# EthernetShield.net
KiCad netlist of a schematic drawn in EAGLE
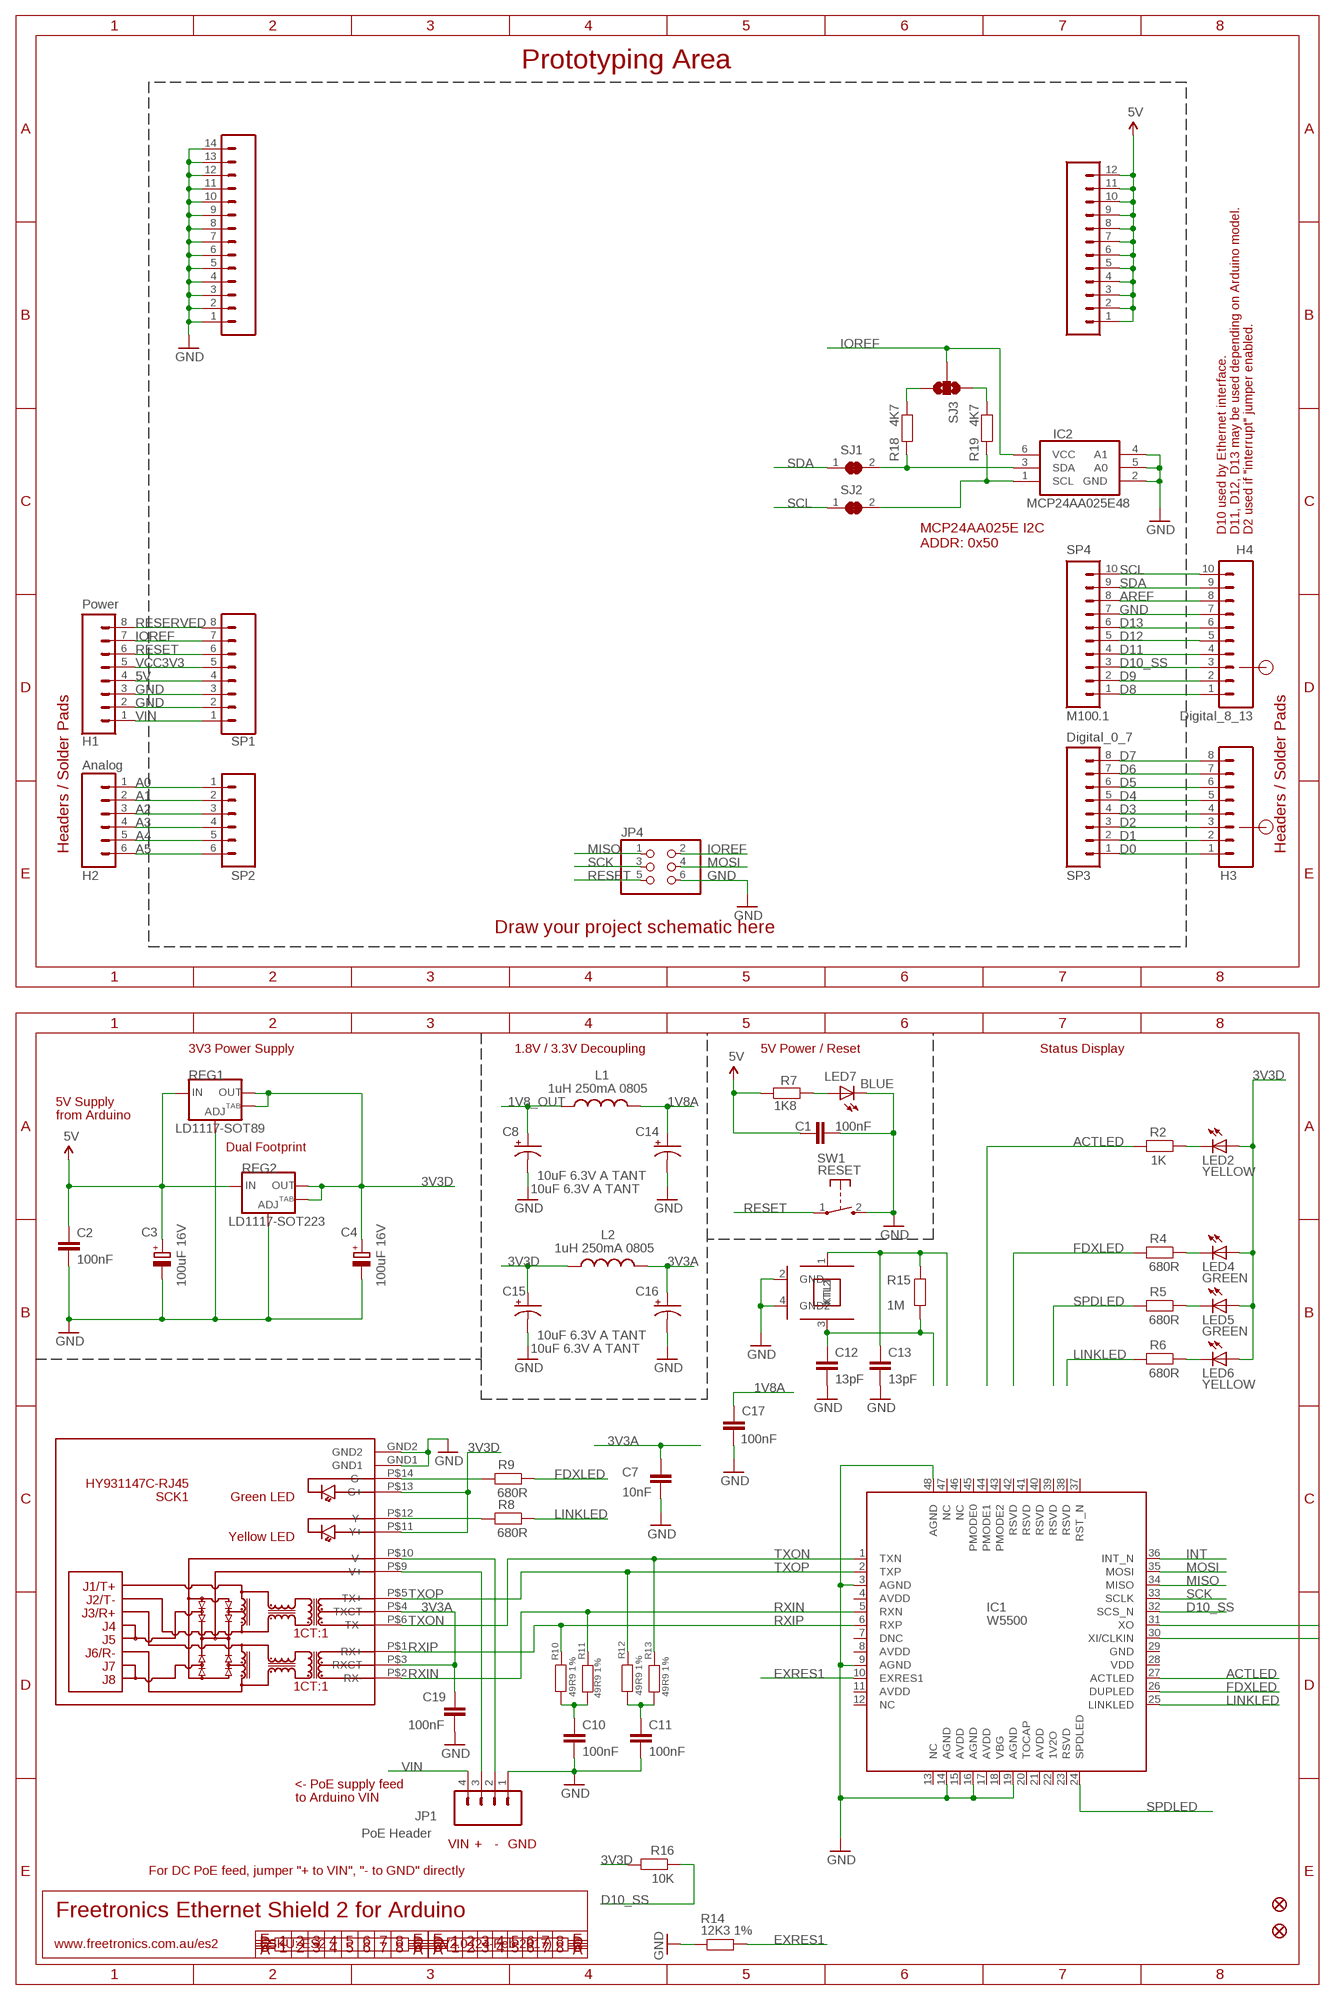
[diagram p0: schematic, sheet 1]

(export (version "E")
  (design (tool "Eeschema 10.0.6"))
  (components
    (comp (ref "C1")
      (value "100nF")
      (footprint "eagle-import:0603")
      (libsource (lib "eagle-import") (part "CAP0603"))
    )
    (comp (ref "C2")
      (value "100nF")
      (footprint "eagle-import:0603")
      (libsource (lib "eagle-import") (part "CAP0603"))
    )
    (comp (ref "C3")
      (value "100uF 16V")
      (footprint "eagle-import:PANASONIC_D")
      (libsource (lib "eagle-import") (part "CPOL-EUD"))
    )
    (comp (ref "C4")
      (value "100uF 16V")
      (footprint "eagle-import:PANASONIC_D")
      (libsource (lib "eagle-import") (part "CPOL-EUD"))
    )
    (comp (ref "C7")
      (value "10nF")
      (footprint "eagle-import:0603")
      (libsource (lib "eagle-import") (part "CAP0603"))
    )
    (comp (ref "C8")
      (value "10uF 6.3V A TANT")
      (footprint "eagle-import:EIA3216")
      (libsource (lib "eagle-import") (part "CAP_POL1206"))
    )
    (comp (ref "C10")
      (value "100nF")
      (footprint "eagle-import:0603")
      (libsource (lib "eagle-import") (part "CAP0603"))
    )
    (comp (ref "C11")
      (value "100nF")
      (footprint "eagle-import:0603")
      (libsource (lib "eagle-import") (part "CAP0603"))
    )
    (comp (ref "C12")
      (value "13pF")
      (footprint "eagle-import:0603")
      (libsource (lib "eagle-import") (part "CAP0603"))
    )
    (comp (ref "C13")
      (value "13pF")
      (footprint "eagle-import:0603")
      (libsource (lib "eagle-import") (part "CAP0603"))
    )
    (comp (ref "C14")
      (value "10uF 6.3V A TANT")
      (footprint "eagle-import:EIA3216")
      (libsource (lib "eagle-import") (part "CAP_POL1206"))
    )
    (comp (ref "C15")
      (value "10uF 6.3V A TANT")
      (footprint "eagle-import:EIA3216")
      (libsource (lib "eagle-import") (part "CAP_POL1206"))
    )
    (comp (ref "C16")
      (value "10uF 6.3V A TANT")
      (footprint "eagle-import:EIA3216")
      (libsource (lib "eagle-import") (part "CAP_POL1206"))
    )
    (comp (ref "C17")
      (value "100nF")
      (footprint "eagle-import:0603")
      (libsource (lib "eagle-import") (part "CAP0603"))
    )
    (comp (ref "C19")
      (value "100nF")
      (footprint "eagle-import:0603")
      (libsource (lib "eagle-import") (part "CAP0603"))
    )
    (comp (ref "H1")
      (value "Power")
      (footprint "eagle-import:1X08")
      (libsource (lib "eagle-import") (part "M08"))
    )
    (comp (ref "H2")
      (value "Analog")
      (footprint "eagle-import:1X06")
      (libsource (lib "eagle-import") (part "M06SIP"))
    )
    (comp (ref "H3")
      (value "Digital_0_7")
      (footprint "eagle-import:1X08")
      (libsource (lib "eagle-import") (part "M08"))
    )
    (comp (ref "H4")
      (value "Digital_8_13")
      (footprint "eagle-import:1X10")
      (libsource (lib "eagle-import") (part "M100.1"))
    )
    (comp (ref "IC1")
      (value "W5500")
      (footprint "eagle-import:W5500")
      (libsource (lib "eagle-import") (part "W5500"))
    )
    (comp (ref "IC2")
      (value "MCP24AA025E48")
      (footprint "eagle-import:SOT23-6")
      (libsource (lib "eagle-import") (part "MCP24AA025E48"))
    )
    (comp (ref "JP1")
      (value "PoE Header")
      (footprint "eagle-import:1X04")
      (libsource (lib "eagle-import") (part "M04PTH"))
    )
    (comp (ref "JP4")
      (value "PINHD-2X3")
      (footprint "eagle-import:2X03")
      (libsource (lib "eagle-import") (part "PINHD-2X3"))
    )
    (comp (ref "L1")
      (value "1uH 250mA 0805")
      (footprint "eagle-import:L2012C")
      (libsource (lib "eagle-import") (part "L-USL2012C"))
    )
    (comp (ref "L2")
      (value "1uH 250mA 0805")
      (footprint "eagle-import:L2012C")
      (libsource (lib "eagle-import") (part "L-USL2012C"))
    )
    (comp (ref "LED2")
      (value "YELLOW")
      (footprint "eagle-import:LED-0603")
      (libsource (lib "eagle-import") (part "LED0603"))
    )
    (comp (ref "LED4")
      (value "GREEN")
      (footprint "eagle-import:LED-0603")
      (libsource (lib "eagle-import") (part "LED0603"))
    )
    (comp (ref "LED5")
      (value "GREEN")
      (footprint "eagle-import:LED-0603")
      (libsource (lib "eagle-import") (part "LED0603"))
    )
    (comp (ref "LED6")
      (value "YELLOW")
      (footprint "eagle-import:LED-0603")
      (libsource (lib "eagle-import") (part "LED0603"))
    )
    (comp (ref "LED7")
      (value "BLUE")
      (footprint "eagle-import:LED-0603")
      (libsource (lib "eagle-import") (part "LED0603"))
    )
    (comp (ref "PADS_5V")
      (value "M12PTH")
      (footprint "eagle-import:1X12")
      (libsource (lib "eagle-import") (part "M12PTH"))
    )
    (comp (ref "PADS_GND")
      (value "M14")
      (footprint "eagle-import:1X14")
      (libsource (lib "eagle-import") (part "M14"))
    )
    (comp (ref "R2")
      (value "1K")
      (footprint "eagle-import:0603")
      (libsource (lib "eagle-import") (part "RESISTOR0603"))
    )
    (comp (ref "R4")
      (value "680R")
      (footprint "eagle-import:0603")
      (libsource (lib "eagle-import") (part "RESISTOR0603"))
    )
    (comp (ref "R5")
      (value "680R")
      (footprint "eagle-import:0603")
      (libsource (lib "eagle-import") (part "RESISTOR0603"))
    )
    (comp (ref "R6")
      (value "680R")
      (footprint "eagle-import:0603")
      (libsource (lib "eagle-import") (part "RESISTOR0603"))
    )
    (comp (ref "R7")
      (value "1K8")
      (footprint "eagle-import:0603")
      (libsource (lib "eagle-import") (part "RESISTOR0603"))
    )
    (comp (ref "R8")
      (value "680R")
      (footprint "eagle-import:0603")
      (libsource (lib "eagle-import") (part "RESISTOR0603"))
    )
    (comp (ref "R9")
      (value "680R")
      (footprint "eagle-import:0603")
      (libsource (lib "eagle-import") (part "RESISTOR0603"))
    )
    (comp (ref "R10")
      (value "49R9 1%")
      (footprint "eagle-import:0603")
      (libsource (lib "eagle-import") (part "RESISTOR0603"))
    )
    (comp (ref "R11")
      (value "49R9 1%")
      (footprint "eagle-import:0603")
      (libsource (lib "eagle-import") (part "RESISTOR0603"))
    )
    (comp (ref "R12")
      (value "49R9 1%")
      (footprint "eagle-import:0603")
      (libsource (lib "eagle-import") (part "RESISTOR0603"))
    )
    (comp (ref "R13")
      (value "49R9 1%")
      (footprint "eagle-import:0603")
      (libsource (lib "eagle-import") (part "RESISTOR0603"))
    )
    (comp (ref "R14")
      (value "12K3 1%")
      (footprint "eagle-import:0603")
      (libsource (lib "eagle-import") (part "RESISTOR0603"))
    )
    (comp (ref "R15")
      (value "1M")
      (footprint "eagle-import:0603")
      (libsource (lib "eagle-import") (part "RESISTOR0603"))
    )
    (comp (ref "R16")
      (value "10K")
      (footprint "eagle-import:0603")
      (libsource (lib "eagle-import") (part "RESISTOR0603"))
    )
    (comp (ref "R18")
      (value "4K7")
      (footprint "eagle-import:0603")
      (libsource (lib "eagle-import") (part "freetronics-master-v1.1_RESISTOR0603"))
    )
    (comp (ref "R19")
      (value "4K7")
      (footprint "eagle-import:0603")
      (libsource (lib "eagle-import") (part "freetronics-master-v1.1_RESISTOR0603"))
    )
    (comp (ref "REG1")
      (value "LD1117-SOT89")
      (footprint "eagle-import:SOT89")
      (libsource (lib "eagle-import") (part "V_REG_LM1117SOT89"))
    )
    (comp (ref "REG2")
      (value "LD1117-SOT223")
      (footprint "eagle-import:SOT223")
      (libsource (lib "eagle-import") (part "V_REG_LM1117SOT223"))
    )
    (comp (ref "SCK1")
      (value "HY931147C-RJ45")
      (footprint "eagle-import:HY931147C")
      (libsource (lib "eagle-import") (part "HY931147C-RJ45"))
    )
    (comp (ref "SJ1")
      (value "SJCN")
      (footprint "eagle-import:SJC")
      (libsource (lib "eagle-import") (part "SJCN"))
    )
    (comp (ref "SJ2")
      (value "SJCN")
      (footprint "eagle-import:SJC")
      (libsource (lib "eagle-import") (part "SJCN"))
    )
    (comp (ref "SJ3")
      (value "SOLDERJUMPER_2WAYT")
      (footprint "eagle-import:SJ_2")
      (libsource (lib "eagle-import") (part "SOLDERJUMPER_2WAYT"))
    )
    (comp (ref "SP1")
      (value "M08")
      (footprint "eagle-import:1X08")
      (libsource (lib "eagle-import") (part "M08"))
    )
    (comp (ref "SP2")
      (value "Analog")
      (footprint "eagle-import:1X06")
      (libsource (lib "eagle-import") (part "M06SIP"))
    )
    (comp (ref "SP3")
      (value "Digital_0_7")
      (footprint "eagle-import:1X08")
      (libsource (lib "eagle-import") (part "M08"))
    )
    (comp (ref "SP4")
      (value "M100.1")
      (footprint "eagle-import:1X10")
      (libsource (lib "eagle-import") (part "M100.1"))
    )
    (comp (ref "SW1")
      (value "RESET")
      (footprint "eagle-import:TACTILE_SWITCH_SMD_2PIN_TINY")
      (libsource (lib "eagle-import") (part "TAC_SWITCH_2PIN"))
    )
    (comp (ref "U$6")
      (value "FIDUCIAL1X2.5")
      (footprint "eagle-import:FIDUCIAL-1X2.5")
      (libsource (lib "eagle-import") (part "FIDUCIAL1X2.5"))
    )
    (comp (ref "U$8")
      (value "FIDUCIAL1X2.5")
      (footprint "eagle-import:FIDUCIAL-1X2.5")
      (libsource (lib "eagle-import") (part "FIDUCIAL1X2.5"))
    )
    (comp (ref "XTL1")
      (value "25MHZ")
      (footprint "eagle-import:CRYSTAL-SMD-3X2")
      (libsource (lib "eagle-import") (part "CRYSTAL-GND3X2"))
    )
  )
  (nets
    (net (code "1") (name "/1V8A") (class "Default")
      (node (ref "C14") (pin "A") (pinfunction "+_A") (pintype "passive"))
      (node (ref "C17") (pin "1") (pinfunction "1_1") (pintype "passive"))
      (node (ref "L1") (pin "2") (pinfunction "2_2") (pintype "passive"))
    )
    (net (code "2") (name "/1V8_OUT") (class "Default")
      (node (ref "C8") (pin "A") (pinfunction "+_A") (pintype "passive"))
      (node (ref "L1") (pin "1") (pinfunction "1_1") (pintype "passive"))
    )
    (net (code "3") (name "/3V3A") (class "Default")
      (node (ref "C16") (pin "A") (pinfunction "+_A") (pintype "passive"))
      (node (ref "C19") (pin "1") (pinfunction "1_1") (pintype "passive"))
      (node (ref "C7") (pin "1") (pinfunction "1_1") (pintype "passive"))
      (node (ref "L2") (pin "2") (pinfunction "2_2") (pintype "passive"))
      (node (ref "SCK1") (pin "P$3") (pinfunction "RXCT_P$3") (pintype "bidirectional"))
      (node (ref "SCK1") (pin "P$4") (pinfunction "TXCT_P$4") (pintype "bidirectional"))
    )
    (net (code "4") (name "/3V3D") (class "Default")
      (node (ref "C15") (pin "A") (pinfunction "+_A") (pintype "passive"))
      (node (ref "C4") (pin "+") (pinfunction "+_+") (pintype "passive"))
      (node (ref "L2") (pin "1") (pinfunction "1_1") (pintype "passive"))
      (node (ref "LED2") (pin "A") (pinfunction "A_A") (pintype "passive"))
      (node (ref "LED4") (pin "A") (pinfunction "A_A") (pintype "passive"))
      (node (ref "LED5") (pin "A") (pinfunction "A_A") (pintype "passive"))
      (node (ref "LED6") (pin "A") (pinfunction "A_A") (pintype "passive"))
      (node (ref "R16") (pin "2") (pinfunction "2_2") (pintype "passive"))
      (node (ref "REG1") (pin "2") (pinfunction "OUT_2") (pintype "output"))
      (node (ref "REG1") (pin "4") (pinfunction "OUT_4") (pintype "output"))
      (node (ref "REG2") (pin "2") (pinfunction "OUT_2") (pintype "output"))
      (node (ref "REG2") (pin "4") (pinfunction "OUT_4") (pintype "output"))
      (node (ref "SCK1") (pin "P$11") (pinfunction "Y+_P$11") (pintype "bidirectional"))
      (node (ref "SCK1") (pin "P$13") (pinfunction "G+_P$13") (pintype "bidirectional"))
    )
    (net (code "5") (name "/A0") (class "Default")
      (node (ref "H2") (pin "1") (pinfunction "1_1") (pintype "passive"))
      (node (ref "SP2") (pin "1") (pinfunction "1_1") (pintype "passive"))
    )
    (net (code "6") (name "/A1") (class "Default")
      (node (ref "H2") (pin "2") (pinfunction "2_2") (pintype "passive"))
      (node (ref "SP2") (pin "2") (pinfunction "2_2") (pintype "passive"))
    )
    (net (code "7") (name "/A2") (class "Default")
      (node (ref "H2") (pin "3") (pinfunction "3_3") (pintype "passive"))
      (node (ref "SP2") (pin "3") (pinfunction "3_3") (pintype "passive"))
    )
    (net (code "8") (name "/A3") (class "Default")
      (node (ref "H2") (pin "4") (pinfunction "4_4") (pintype "passive"))
      (node (ref "SP2") (pin "4") (pinfunction "4_4") (pintype "passive"))
    )
    (net (code "9") (name "/A4") (class "Default")
      (node (ref "H2") (pin "5") (pinfunction "5_5") (pintype "passive"))
      (node (ref "SP2") (pin "5") (pinfunction "5_5") (pintype "passive"))
    )
    (net (code "10") (name "/A5") (class "Default")
      (node (ref "H2") (pin "6") (pinfunction "6_6") (pintype "passive"))
      (node (ref "SP2") (pin "6") (pinfunction "6_6") (pintype "passive"))
    )
    (net (code "11") (name "/ACTLED") (class "Default")
      (node (ref "IC1") (pin "27") (pinfunction "ACTLED_27") (pintype "passive"))
      (node (ref "R2") (pin "2") (pinfunction "2_2") (pintype "passive"))
    )
    (net (code "12") (name "/AREF") (class "Default")
      (node (ref "H4") (pin "8") (pinfunction "8_8") (pintype "passive"))
      (node (ref "SP4") (pin "8") (pinfunction "8_8") (pintype "passive"))
    )
    (net (code "13") (name "/D0") (class "Default")
      (node (ref "H3") (pin "1") (pinfunction "1_1") (pintype "passive"))
      (node (ref "SP3") (pin "1") (pinfunction "1_1") (pintype "passive"))
    )
    (net (code "14") (name "/D1") (class "Default")
      (node (ref "H3") (pin "2") (pinfunction "2_2") (pintype "passive"))
      (node (ref "SP3") (pin "2") (pinfunction "2_2") (pintype "passive"))
    )
    (net (code "15") (name "/D2") (class "Default")
      (node (ref "H3") (pin "3") (pinfunction "3_3") (pintype "passive"))
      (node (ref "SP3") (pin "3") (pinfunction "3_3") (pintype "passive"))
    )
    (net (code "16") (name "/D3") (class "Default")
      (node (ref "H3") (pin "4") (pinfunction "4_4") (pintype "passive"))
      (node (ref "SP3") (pin "4") (pinfunction "4_4") (pintype "passive"))
    )
    (net (code "17") (name "/D4") (class "Default")
      (node (ref "H3") (pin "5") (pinfunction "5_5") (pintype "passive"))
      (node (ref "SP3") (pin "5") (pinfunction "5_5") (pintype "passive"))
    )
    (net (code "18") (name "/D5") (class "Default")
      (node (ref "H3") (pin "6") (pinfunction "6_6") (pintype "passive"))
      (node (ref "SP3") (pin "6") (pinfunction "6_6") (pintype "passive"))
    )
    (net (code "19") (name "/D6") (class "Default")
      (node (ref "H3") (pin "7") (pinfunction "7_7") (pintype "passive"))
      (node (ref "SP3") (pin "7") (pinfunction "7_7") (pintype "passive"))
    )
    (net (code "20") (name "/D7") (class "Default")
      (node (ref "H3") (pin "8") (pinfunction "8_8") (pintype "passive"))
      (node (ref "SP3") (pin "8") (pinfunction "8_8") (pintype "passive"))
    )
    (net (code "21") (name "/D8") (class "Default")
      (node (ref "H4") (pin "1") (pinfunction "1_1") (pintype "passive"))
      (node (ref "SP4") (pin "1") (pinfunction "1_1") (pintype "passive"))
    )
    (net (code "22") (name "/D9") (class "Default")
      (node (ref "H4") (pin "2") (pinfunction "2_2") (pintype "passive"))
      (node (ref "SP4") (pin "2") (pinfunction "2_2") (pintype "passive"))
    )
    (net (code "23") (name "/D10_SS") (class "Default")
      (node (ref "H4") (pin "3") (pinfunction "3_3") (pintype "passive"))
      (node (ref "IC1") (pin "32") (pinfunction "SCS_N_32") (pintype "passive"))
      (node (ref "R16") (pin "1") (pinfunction "1_1") (pintype "passive"))
      (node (ref "SP4") (pin "3") (pinfunction "3_3") (pintype "passive"))
    )
    (net (code "24") (name "/D11") (class "Default")
      (node (ref "H4") (pin "4") (pinfunction "4_4") (pintype "passive"))
      (node (ref "SP4") (pin "4") (pinfunction "4_4") (pintype "passive"))
    )
    (net (code "25") (name "/D12") (class "Default")
      (node (ref "H4") (pin "5") (pinfunction "5_5") (pintype "passive"))
      (node (ref "SP4") (pin "5") (pinfunction "5_5") (pintype "passive"))
    )
    (net (code "26") (name "/D13") (class "Default")
      (node (ref "H4") (pin "6") (pinfunction "6_6") (pintype "passive"))
      (node (ref "SP4") (pin "6") (pinfunction "6_6") (pintype "passive"))
    )
    (net (code "27") (name "/EXRES1") (class "Default")
      (node (ref "IC1") (pin "10") (pinfunction "EXRES1_10") (pintype "passive"))
      (node (ref "R14") (pin "2") (pinfunction "2_2") (pintype "passive"))
    )
    (net (code "28") (name "/FDXLED") (class "Default")
      (node (ref "IC1") (pin "26") (pinfunction "DUPLED_26") (pintype "passive"))
      (node (ref "R4") (pin "2") (pinfunction "2_2") (pintype "passive"))
      (node (ref "R9") (pin "1") (pinfunction "1_1") (pintype "passive"))
    )
    (net (code "29") (name "/INT") (class "Default")
      (node (ref "IC1") (pin "36") (pinfunction "INT_N_36") (pintype "passive"))
    )
    (net (code "30") (name "/IOREF") (class "Default")
      (node (ref "H1") (pin "7") (pinfunction "7_7") (pintype "passive"))
      (node (ref "IC2") (pin "6") (pinfunction "VCC_6") (pintype "power_in"))
      (node (ref "JP4") (pin "2") (pinfunction "2_2") (pintype "passive"))
      (node (ref "SJ3") (pin "2") (pinfunction "2_2") (pintype "passive"))
      (node (ref "SP1") (pin "7") (pinfunction "7_7") (pintype "passive"))
    )
    (net (code "31") (name "/LINKLED") (class "Default")
      (node (ref "IC1") (pin "25") (pinfunction "LINKLED_25") (pintype "passive"))
      (node (ref "R6") (pin "2") (pinfunction "2_2") (pintype "passive"))
      (node (ref "R8") (pin "1") (pinfunction "1_1") (pintype "passive"))
    )
    (net (code "32") (name "/MISO") (class "Default")
      (node (ref "IC1") (pin "34") (pinfunction "MISO_34") (pintype "passive"))
      (node (ref "JP4") (pin "1") (pinfunction "1_1") (pintype "passive"))
    )
    (net (code "33") (name "/MOSI") (class "Default")
      (node (ref "IC1") (pin "35") (pinfunction "MOSI_35") (pintype "passive"))
      (node (ref "JP4") (pin "4") (pinfunction "4_4") (pintype "passive"))
    )
    (net (code "34") (name "/RESERVED") (class "Default")
      (node (ref "H1") (pin "8") (pinfunction "8_8") (pintype "passive"))
      (node (ref "SP1") (pin "8") (pinfunction "8_8") (pintype "passive"))
    )
    (net (code "35") (name "/RESET") (class "Default")
      (node (ref "H1") (pin "6") (pinfunction "6_6") (pintype "passive"))
      (node (ref "JP4") (pin "5") (pinfunction "5_5") (pintype "passive"))
      (node (ref "SP1") (pin "6") (pinfunction "6_6") (pintype "passive"))
      (node (ref "SW1") (pin "1") (pinfunction "P_1") (pintype "passive"))
    )
    (net (code "36") (name "/RXIN") (class "Default")
      (node (ref "IC1") (pin "5") (pinfunction "RXN_5") (pintype "passive"))
      (node (ref "R11") (pin "1") (pinfunction "1_1") (pintype "passive"))
      (node (ref "SCK1") (pin "P$2") (pinfunction "RX-_P$2") (pintype "bidirectional"))
    )
    (net (code "37") (name "/RXIP") (class "Default")
      (node (ref "IC1") (pin "6") (pinfunction "RXP_6") (pintype "passive"))
      (node (ref "R10") (pin "2") (pinfunction "2_2") (pintype "passive"))
      (node (ref "SCK1") (pin "P$1") (pinfunction "RX+_P$1") (pintype "bidirectional"))
    )
    (net (code "38") (name "/SCK") (class "Default")
      (node (ref "IC1") (pin "33") (pinfunction "SCLK_33") (pintype "passive"))
      (node (ref "JP4") (pin "3") (pinfunction "3_3") (pintype "passive"))
    )
    (net (code "39") (name "/SCL") (class "Default")
      (node (ref "H4") (pin "10") (pinfunction "10_10") (pintype "passive"))
      (node (ref "SJ2") (pin "1") (pinfunction "1_1") (pintype "passive"))
      (node (ref "SP4") (pin "10") (pinfunction "10_10") (pintype "passive"))
    )
    (net (code "40") (name "/SDA") (class "Default")
      (node (ref "H4") (pin "9") (pinfunction "9_9") (pintype "passive"))
      (node (ref "SJ1") (pin "1") (pinfunction "1_1") (pintype "passive"))
      (node (ref "SP4") (pin "9") (pinfunction "9_9") (pintype "passive"))
    )
    (net (code "41") (name "/SPDLED") (class "Default")
      (node (ref "IC1") (pin "24") (pinfunction "SPDLED_24") (pintype "passive"))
      (node (ref "R5") (pin "2") (pinfunction "2_2") (pintype "passive"))
    )
    (net (code "42") (name "/TXON") (class "Default")
      (node (ref "IC1") (pin "1") (pinfunction "TXN_1") (pintype "passive"))
      (node (ref "R13") (pin "1") (pinfunction "1_1") (pintype "passive"))
      (node (ref "SCK1") (pin "P$6") (pinfunction "TX-_P$6") (pintype "bidirectional"))
    )
    (net (code "43") (name "/TXOP") (class "Default")
      (node (ref "IC1") (pin "2") (pinfunction "TXP_2") (pintype "passive"))
      (node (ref "R12") (pin "2") (pinfunction "2_2") (pintype "passive"))
      (node (ref "SCK1") (pin "P$5") (pinfunction "TX+_P$5") (pintype "bidirectional"))
    )
    (net (code "44") (name "/VCC3V3") (class "Default")
      (node (ref "H1") (pin "5") (pinfunction "5_5") (pintype "passive"))
      (node (ref "SP1") (pin "5") (pinfunction "5_5") (pintype "passive"))
    )
    (net (code "45") (name "/VIN") (class "Default")
      (node (ref "H1") (pin "1") (pinfunction "1_1") (pintype "passive"))
      (node (ref "JP1") (pin "4") (pinfunction "4_4") (pintype "passive"))
      (node (ref "SP1") (pin "1") (pinfunction "1_1") (pintype "passive"))
    )
    (net (code "46") (name "5V") (class "Default")
      (node (ref "C1") (pin "1") (pinfunction "1_1") (pintype "passive"))
      (node (ref "C2") (pin "1") (pinfunction "1_1") (pintype "passive"))
      (node (ref "C3") (pin "+") (pinfunction "+_+") (pintype "passive"))
      (node (ref "H1") (pin "4") (pinfunction "4_4") (pintype "passive"))
      (node (ref "PADS_5V") (pin "1") (pinfunction "1_1") (pintype "passive"))
      (node (ref "PADS_5V") (pin "10") (pinfunction "10_10") (pintype "passive"))
      (node (ref "PADS_5V") (pin "11") (pinfunction "11_11") (pintype "passive"))
      (node (ref "PADS_5V") (pin "12") (pinfunction "12_12") (pintype "passive"))
      (node (ref "PADS_5V") (pin "2") (pinfunction "2_2") (pintype "passive"))
      (node (ref "PADS_5V") (pin "3") (pinfunction "3_3") (pintype "passive"))
      (node (ref "PADS_5V") (pin "4") (pinfunction "4_4") (pintype "passive"))
      (node (ref "PADS_5V") (pin "5") (pinfunction "5_5") (pintype "passive"))
      (node (ref "PADS_5V") (pin "6") (pinfunction "6_6") (pintype "passive"))
      (node (ref "PADS_5V") (pin "7") (pinfunction "7_7") (pintype "passive"))
      (node (ref "PADS_5V") (pin "8") (pinfunction "8_8") (pintype "passive"))
      (node (ref "PADS_5V") (pin "9") (pinfunction "9_9") (pintype "passive"))
      (node (ref "R7") (pin "1") (pinfunction "1_1") (pintype "passive"))
      (node (ref "REG1") (pin "3") (pinfunction "IN_3") (pintype "input"))
      (node (ref "REG2") (pin "3") (pinfunction "IN_3") (pintype "input"))
      (node (ref "SP1") (pin "4") (pinfunction "4_4") (pintype "passive"))
    )
    (net (code "47") (name "GND") (class "Default")
      (node (ref "C1") (pin "2") (pinfunction "2_2") (pintype "passive"))
      (node (ref "C10") (pin "2") (pinfunction "2_2") (pintype "passive"))
      (node (ref "C11") (pin "2") (pinfunction "2_2") (pintype "passive"))
      (node (ref "C12") (pin "2") (pinfunction "2_2") (pintype "passive"))
      (node (ref "C13") (pin "2") (pinfunction "2_2") (pintype "passive"))
      (node (ref "C14") (pin "C") (pinfunction "-_C") (pintype "passive"))
      (node (ref "C15") (pin "C") (pinfunction "-_C") (pintype "passive"))
      (node (ref "C16") (pin "C") (pinfunction "-_C") (pintype "passive"))
      (node (ref "C17") (pin "2") (pinfunction "2_2") (pintype "passive"))
      (node (ref "C19") (pin "2") (pinfunction "2_2") (pintype "passive"))
      (node (ref "C2") (pin "2") (pinfunction "2_2") (pintype "passive"))
      (node (ref "C3") (pin "-") (pinfunction "-_-") (pintype "passive"))
      (node (ref "C4") (pin "-") (pinfunction "-_-") (pintype "passive"))
      (node (ref "C7") (pin "2") (pinfunction "2_2") (pintype "passive"))
      (node (ref "C8") (pin "C") (pinfunction "-_C") (pintype "passive"))
      (node (ref "H1") (pin "2") (pinfunction "2_2") (pintype "passive"))
      (node (ref "H1") (pin "3") (pinfunction "3_3") (pintype "passive"))
      (node (ref "H4") (pin "7") (pinfunction "7_7") (pintype "passive"))
      (node (ref "IC1") (pin "14") (pinfunction "AGND_14") (pintype "passive"))
      (node (ref "IC1") (pin "16") (pinfunction "AGND_16") (pintype "passive"))
      (node (ref "IC1") (pin "19") (pinfunction "AGND_19") (pintype "passive"))
      (node (ref "IC1") (pin "3") (pinfunction "AGND_3") (pintype "passive"))
      (node (ref "IC1") (pin "48") (pinfunction "AGND_48") (pintype "passive"))
      (node (ref "IC1") (pin "9") (pinfunction "AGND_9") (pintype "passive"))
      (node (ref "IC2") (pin "2") (pinfunction "GND_2") (pintype "power_in"))
      (node (ref "IC2") (pin "4") (pinfunction "A1_4") (pintype "input"))
      (node (ref "IC2") (pin "5") (pinfunction "A0_5") (pintype "input"))
      (node (ref "JP1") (pin "1") (pinfunction "1_1") (pintype "passive"))
      (node (ref "JP4") (pin "6") (pinfunction "6_6") (pintype "passive"))
      (node (ref "LED7") (pin "C") (pinfunction "C_C") (pintype "passive"))
      (node (ref "PADS_GND") (pin "1") (pinfunction "1_1") (pintype "passive"))
      (node (ref "PADS_GND") (pin "10") (pinfunction "10_10") (pintype "passive"))
      (node (ref "PADS_GND") (pin "11") (pinfunction "11_11") (pintype "passive"))
      (node (ref "PADS_GND") (pin "12") (pinfunction "12_12") (pintype "passive"))
      (node (ref "PADS_GND") (pin "13") (pinfunction "13_13") (pintype "passive"))
      (node (ref "PADS_GND") (pin "14") (pinfunction "14_14") (pintype "passive"))
      (node (ref "PADS_GND") (pin "2") (pinfunction "2_2") (pintype "passive"))
      (node (ref "PADS_GND") (pin "3") (pinfunction "3_3") (pintype "passive"))
      (node (ref "PADS_GND") (pin "4") (pinfunction "4_4") (pintype "passive"))
      (node (ref "PADS_GND") (pin "5") (pinfunction "5_5") (pintype "passive"))
      (node (ref "PADS_GND") (pin "6") (pinfunction "6_6") (pintype "passive"))
      (node (ref "PADS_GND") (pin "7") (pinfunction "7_7") (pintype "passive"))
      (node (ref "PADS_GND") (pin "8") (pinfunction "8_8") (pintype "passive"))
      (node (ref "PADS_GND") (pin "9") (pinfunction "9_9") (pintype "passive"))
      (node (ref "R14") (pin "1") (pinfunction "1_1") (pintype "passive"))
      (node (ref "REG1") (pin "1") (pinfunction "ADJ_1") (pintype "input"))
      (node (ref "REG2") (pin "1") (pinfunction "ADJ_1") (pintype "input"))
      (node (ref "SCK1") (pin "GND1") (pinfunction "GND1_GND1") (pintype "bidirectional"))
      (node (ref "SCK1") (pin "GND2") (pinfunction "GND2_GND2") (pintype "bidirectional"))
      (node (ref "SP1") (pin "2") (pinfunction "2_2") (pintype "passive"))
      (node (ref "SP1") (pin "3") (pinfunction "3_3") (pintype "passive"))
      (node (ref "SP4") (pin "7") (pinfunction "7_7") (pintype "passive"))
      (node (ref "SW1") (pin "2") (pinfunction "S_2") (pintype "passive"))
      (node (ref "XTL1") (pin "2") (pinfunction "GND_2") (pintype "bidirectional"))
      (node (ref "XTL1") (pin "4") (pinfunction "GND2_4") (pintype "bidirectional"))
    )
    (net (code "48") (name "Net-(C10-Pad1)") (class "Default")
      (node (ref "C10") (pin "1") (pinfunction "1_1") (pintype "passive"))
      (node (ref "R10") (pin "1") (pinfunction "1_1") (pintype "passive"))
      (node (ref "R11") (pin "2") (pinfunction "2_2") (pintype "passive"))
    )
    (net (code "49") (name "Net-(C11-Pad1)") (class "Default")
      (node (ref "C11") (pin "1") (pinfunction "1_1") (pintype "passive"))
      (node (ref "R12") (pin "1") (pinfunction "1_1") (pintype "passive"))
      (node (ref "R13") (pin "2") (pinfunction "2_2") (pintype "passive"))
    )
    (net (code "50") (name "Net-(IC2-SCL)") (class "Default")
      (node (ref "IC2") (pin "1") (pinfunction "SCL_1") (pintype "bidirectional"))
      (node (ref "R19") (pin "2") (pinfunction "2_2") (pintype "passive"))
      (node (ref "SJ2") (pin "2") (pinfunction "2_2") (pintype "passive"))
    )
    (net (code "51") (name "Net-(IC2-SDA)") (class "Default")
      (node (ref "IC2") (pin "3") (pinfunction "SDA_3") (pintype "bidirectional"))
      (node (ref "R18") (pin "2") (pinfunction "2_2") (pintype "passive"))
      (node (ref "SJ1") (pin "2") (pinfunction "2_2") (pintype "passive"))
    )
    (net (code "52") (name "Net-(LED2-PadC)") (class "Default")
      (node (ref "LED2") (pin "C") (pinfunction "C_C") (pintype "passive"))
      (node (ref "R2") (pin "1") (pinfunction "1_1") (pintype "passive"))
    )
    (net (code "53") (name "Net-(LED4-PadC)") (class "Default")
      (node (ref "LED4") (pin "C") (pinfunction "C_C") (pintype "passive"))
      (node (ref "R4") (pin "1") (pinfunction "1_1") (pintype "passive"))
    )
    (net (code "54") (name "Net-(LED5-PadC)") (class "Default")
      (node (ref "LED5") (pin "C") (pinfunction "C_C") (pintype "passive"))
      (node (ref "R5") (pin "1") (pinfunction "1_1") (pintype "passive"))
    )
    (net (code "55") (name "Net-(LED6-PadC)") (class "Default")
      (node (ref "LED6") (pin "C") (pinfunction "C_C") (pintype "passive"))
      (node (ref "R6") (pin "1") (pinfunction "1_1") (pintype "passive"))
    )
    (net (code "56") (name "Net-(LED7-PadA)") (class "Default")
      (node (ref "LED7") (pin "A") (pinfunction "A_A") (pintype "passive"))
      (node (ref "R7") (pin "2") (pinfunction "2_2") (pintype "passive"))
    )
    (net (code "57") (name "Net-(R18-Pad1)") (class "Default")
      (node (ref "R18") (pin "1") (pinfunction "1_1") (pintype "passive"))
      (node (ref "SJ3") (pin "3") (pinfunction "3_3") (pintype "passive"))
    )
    (net (code "58") (name "Net-(R19-Pad1)") (class "Default")
      (node (ref "R19") (pin "1") (pinfunction "1_1") (pintype "passive"))
      (node (ref "SJ3") (pin "1") (pinfunction "1_1") (pintype "passive"))
    )
    (net (code "59") (name "Net-(SCK1-G-)") (class "Default")
      (node (ref "R9") (pin "2") (pinfunction "2_2") (pintype "passive"))
      (node (ref "SCK1") (pin "P$14") (pinfunction "G-_P$14") (pintype "bidirectional"))
    )
    (net (code "60") (name "Net-(SCK1-V+)") (class "Default")
      (node (ref "JP1") (pin "3") (pinfunction "3_3") (pintype "passive"))
      (node (ref "SCK1") (pin "P$9") (pinfunction "V+_P$9") (pintype "bidirectional"))
    )
    (net (code "61") (name "Net-(SCK1-V-)") (class "Default")
      (node (ref "JP1") (pin "2") (pinfunction "2_2") (pintype "passive"))
      (node (ref "SCK1") (pin "P$10") (pinfunction "V-_P$10") (pintype "bidirectional"))
    )
    (net (code "62") (name "Net-(SCK1-Y-)") (class "Default")
      (node (ref "R8") (pin "2") (pinfunction "2_2") (pintype "passive"))
      (node (ref "SCK1") (pin "P$12") (pinfunction "Y-_P$12") (pintype "bidirectional"))
    )
    (net (code "63") (name "Net-(XTL1-XTL1)") (class "Default")
      (node (ref "C13") (pin "1") (pinfunction "1_1") (pintype "passive"))
      (node (ref "R15") (pin "2") (pinfunction "2_2") (pintype "passive"))
      (node (ref "XTL1") (pin "1") (pinfunction "XTL1_1") (pintype "bidirectional"))
    )
    (net (code "64") (name "Net-(XTL1-XTL2)") (class "Default")
      (node (ref "C12") (pin "1") (pinfunction "1_1") (pintype "passive"))
      (node (ref "R15") (pin "1") (pinfunction "1_1") (pintype "passive"))
      (node (ref "XTL1") (pin "3") (pinfunction "XTL2_3") (pintype "bidirectional"))
    )
    (net (code "65") (name "unconnected-(IC1-1V2O-Pad22)") (class "Default")
      (node (ref "IC1") (pin "22") (pinfunction "1V2O_22") (pintype "passive"))
    )
    (net (code "66") (name "unconnected-(IC1-AVDD-Pad4)") (class "Default")
      (node (ref "IC1") (pin "4") (pinfunction "AVDD_4") (pintype "passive"))
    )
    (net (code "67") (name "unconnected-(IC1-AVDD-Pad8)") (class "Default")
      (node (ref "IC1") (pin "8") (pinfunction "AVDD_8") (pintype "passive"))
    )
    (net (code "68") (name "unconnected-(IC1-AVDD-Pad11)") (class "Default")
      (node (ref "IC1") (pin "11") (pinfunction "AVDD_11") (pintype "passive"))
    )
    (net (code "69") (name "unconnected-(IC1-AVDD-Pad15)") (class "Default")
      (node (ref "IC1") (pin "15") (pinfunction "AVDD_15") (pintype "passive"))
    )
    (net (code "70") (name "unconnected-(IC1-AVDD-Pad17)") (class "Default")
      (node (ref "IC1") (pin "17") (pinfunction "AVDD_17") (pintype "passive"))
    )
    (net (code "71") (name "unconnected-(IC1-AVDD-Pad21)") (class "Default")
      (node (ref "IC1") (pin "21") (pinfunction "AVDD_21") (pintype "passive"))
    )
    (net (code "72") (name "unconnected-(IC1-DNC-Pad7)") (class "Default")
      (node (ref "IC1") (pin "7") (pinfunction "DNC_7") (pintype "passive"))
    )
    (net (code "73") (name "unconnected-(IC1-GND-Pad29)") (class "Default")
      (node (ref "IC1") (pin "29") (pinfunction "GND_29") (pintype "passive"))
    )
    (net (code "74") (name "unconnected-(IC1-NC-Pad12)") (class "Default")
      (node (ref "IC1") (pin "12") (pinfunction "NC_12") (pintype "passive"))
    )
    (net (code "75") (name "unconnected-(IC1-NC-Pad13)") (class "Default")
      (node (ref "IC1") (pin "13") (pinfunction "NC_13") (pintype "passive"))
    )
    (net (code "76") (name "unconnected-(IC1-NC-Pad46)") (class "Default")
      (node (ref "IC1") (pin "46") (pinfunction "NC_46") (pintype "passive"))
    )
    (net (code "77") (name "unconnected-(IC1-NC-Pad47)") (class "Default")
      (node (ref "IC1") (pin "47") (pinfunction "NC_47") (pintype "passive"))
    )
    (net (code "78") (name "unconnected-(IC1-PMODE0-Pad45)") (class "Default")
      (node (ref "IC1") (pin "45") (pinfunction "PMODE0_45") (pintype "passive"))
    )
    (net (code "79") (name "unconnected-(IC1-PMODE1-Pad44)") (class "Default")
      (node (ref "IC1") (pin "44") (pinfunction "PMODE1_44") (pintype "passive"))
    )
    (net (code "80") (name "unconnected-(IC1-PMODE2-Pad43)") (class "Default")
      (node (ref "IC1") (pin "43") (pinfunction "PMODE2_43") (pintype "passive"))
    )
    (net (code "81") (name "unconnected-(IC1-RST_N-Pad37)") (class "Default")
      (node (ref "IC1") (pin "37") (pinfunction "RST_N_37") (pintype "passive"))
    )
    (net (code "82") (name "unconnected-(IC1-RSVD-Pad23)") (class "Default")
      (node (ref "IC1") (pin "23") (pinfunction "RSVD_23") (pintype "passive"))
    )
    (net (code "83") (name "unconnected-(IC1-RSVD-Pad38)") (class "Default")
      (node (ref "IC1") (pin "38") (pinfunction "RSVD_38") (pintype "passive"))
    )
    (net (code "84") (name "unconnected-(IC1-RSVD-Pad39)") (class "Default")
      (node (ref "IC1") (pin "39") (pinfunction "RSVD_39") (pintype "passive"))
    )
    (net (code "85") (name "unconnected-(IC1-RSVD-Pad40)") (class "Default")
      (node (ref "IC1") (pin "40") (pinfunction "RSVD_40") (pintype "passive"))
    )
    (net (code "86") (name "unconnected-(IC1-RSVD-Pad41)") (class "Default")
      (node (ref "IC1") (pin "41") (pinfunction "RSVD_41") (pintype "passive"))
    )
    (net (code "87") (name "unconnected-(IC1-RSVD-Pad42)") (class "Default")
      (node (ref "IC1") (pin "42") (pinfunction "RSVD_42") (pintype "passive"))
    )
    (net (code "88") (name "unconnected-(IC1-TOCAP-Pad20)") (class "Default")
      (node (ref "IC1") (pin "20") (pinfunction "TOCAP_20") (pintype "passive"))
    )
    (net (code "89") (name "unconnected-(IC1-VBG-Pad18)") (class "Default")
      (node (ref "IC1") (pin "18") (pinfunction "VBG_18") (pintype "passive"))
    )
    (net (code "90") (name "unconnected-(IC1-VDD-Pad28)") (class "Default")
      (node (ref "IC1") (pin "28") (pinfunction "VDD_28") (pintype "passive"))
    )
    (net (code "91") (name "unconnected-(IC1-XI{slash}CLKIN-Pad30)") (class "Default")
      (node (ref "IC1") (pin "30") (pinfunction "XI/CLKIN_30") (pintype "passive"))
    )
    (net (code "92") (name "unconnected-(IC1-XO-Pad31)") (class "Default")
      (node (ref "IC1") (pin "31") (pinfunction "XO_31") (pintype "passive"))
    )
  )
)
